# ColorMixingLamp.net
KiCad netlist of a schematic drawn in EAGLE
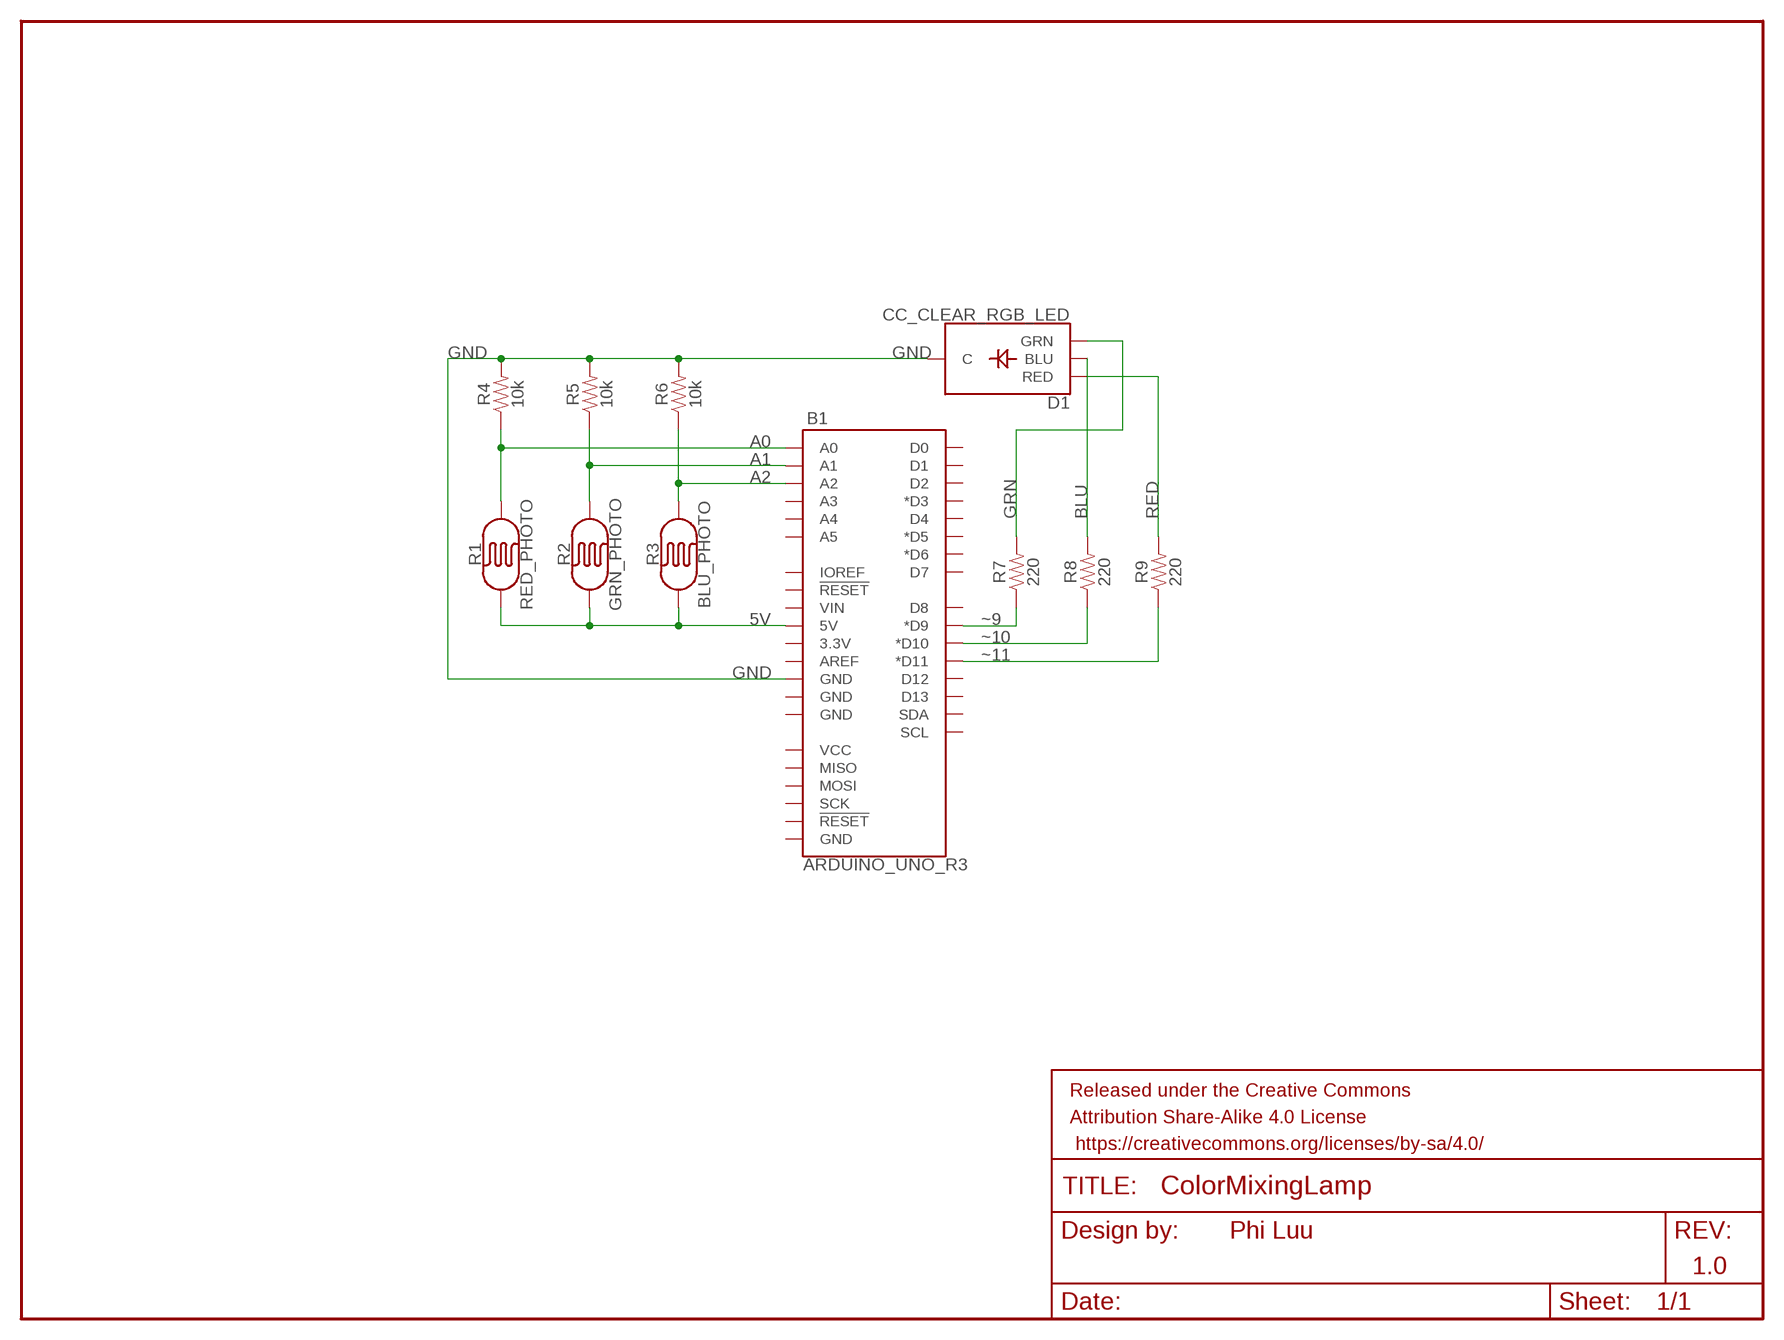
[diagram p0: schematic, sheet 1]

(export (version "E")
  (design (tool "Eeschema 10.0.6"))
  (components
    (comp (ref "B1")
      (value "ARDUINO_UNO_R3")
      (footprint "eagle-import:ARDUINO_R3")
      (libsource (lib "eagle-import") (part "ARDUINO_UNO_R3"))
    )
    (comp (ref "D1")
      (value "CC_CLEAR_RGB_LED")
      (footprint "eagle-import:LED-RGB-THRU")
      (libsource (lib "eagle-import") (part "LED-RGB-CCCLEAR"))
    )
    (comp (ref "FRAME1")
      (value "FRAME-LETTER")
      (footprint "eagle-import:CREATIVE_COMMONS")
      (libsource (lib "eagle-import") (part "FRAME-LETTER"))
    )
    (comp (ref "R1")
      (value "RED_PHOTO")
      (footprint "eagle-import:PHOTOCELL")
      (libsource (lib "eagle-import") (part "PHOTOCELLPTH"))
    )
    (comp (ref "R2")
      (value "GRN_PHOTO")
      (footprint "eagle-import:PHOTOCELL")
      (libsource (lib "eagle-import") (part "PHOTOCELLPTH"))
    )
    (comp (ref "R3")
      (value "BLU_PHOTO")
      (footprint "eagle-import:PHOTOCELL")
      (libsource (lib "eagle-import") (part "PHOTOCELLPTH"))
    )
    (comp (ref "R4")
      (value "10k")
      (footprint "eagle-import:AXIAL-0.3")
      (libsource (lib "eagle-import") (part "10KOHM-HORIZ-1/4W-5%"))
    )
    (comp (ref "R5")
      (value "10k")
      (footprint "eagle-import:AXIAL-0.3")
      (libsource (lib "eagle-import") (part "10KOHM-HORIZ-1/4W-5%"))
    )
    (comp (ref "R6")
      (value "10k")
      (footprint "eagle-import:AXIAL-0.3")
      (libsource (lib "eagle-import") (part "10KOHM-HORIZ-1/4W-5%"))
    )
    (comp (ref "R7")
      (value "220")
      (footprint "eagle-import:AXIAL-0.3")
      (libsource (lib "eagle-import") (part "1KOHM-HORIZ-1/4W-5%"))
    )
    (comp (ref "R8")
      (value "220")
      (footprint "eagle-import:AXIAL-0.3")
      (libsource (lib "eagle-import") (part "1KOHM-HORIZ-1/4W-5%"))
    )
    (comp (ref "R9")
      (value "220")
      (footprint "eagle-import:AXIAL-0.3")
      (libsource (lib "eagle-import") (part "1KOHM-HORIZ-1/4W-5%"))
    )
  )
  (nets
    (net (code "1") (name "/5V") (class "Default")
      (node (ref "B1") (pin "5V") (pinfunction "5V_5V") (pintype "bidirectional"))
      (node (ref "R1") (pin "1") (pinfunction "P$1_1") (pintype "bidirectional"))
      (node (ref "R2") (pin "1") (pinfunction "P$1_1") (pintype "bidirectional"))
      (node (ref "R3") (pin "1") (pinfunction "P$1_1") (pintype "bidirectional"))
    )
    (net (code "2") (name "/A0") (class "Default")
      (node (ref "B1") (pin "A0") (pinfunction "A0_A0") (pintype "bidirectional"))
      (node (ref "R1") (pin "2") (pinfunction "P$2_2") (pintype "bidirectional"))
      (node (ref "R4") (pin "P$1") (pinfunction "1_P$1") (pintype "passive"))
    )
    (net (code "3") (name "/A1") (class "Default")
      (node (ref "B1") (pin "A1") (pinfunction "A1_A1") (pintype "bidirectional"))
      (node (ref "R2") (pin "2") (pinfunction "P$2_2") (pintype "bidirectional"))
      (node (ref "R5") (pin "P$1") (pinfunction "1_P$1") (pintype "passive"))
    )
    (net (code "4") (name "/A2") (class "Default")
      (node (ref "B1") (pin "A2") (pinfunction "A2_A2") (pintype "bidirectional"))
      (node (ref "R3") (pin "2") (pinfunction "P$2_2") (pintype "bidirectional"))
      (node (ref "R6") (pin "P$1") (pinfunction "1_P$1") (pintype "passive"))
    )
    (net (code "5") (name "/BLU") (class "Default")
      (node (ref "D1") (pin "4") (pinfunction "BLU_4") (pintype "bidirectional"))
      (node (ref "R8") (pin "P$2") (pinfunction "2_P$2") (pintype "passive"))
    )
    (net (code "6") (name "/GND") (class "Default")
      (node (ref "B1") (pin "GND@4") (pinfunction "GND_GND@4") (pintype "bidirectional"))
      (node (ref "D1") (pin "2") (pinfunction "C_2") (pintype "bidirectional"))
      (node (ref "R4") (pin "P$2") (pinfunction "2_P$2") (pintype "passive"))
      (node (ref "R5") (pin "P$2") (pinfunction "2_P$2") (pintype "passive"))
      (node (ref "R6") (pin "P$2") (pinfunction "2_P$2") (pintype "passive"))
    )
    (net (code "7") (name "/GRN") (class "Default")
      (node (ref "D1") (pin "3") (pinfunction "GRN_3") (pintype "bidirectional"))
      (node (ref "R7") (pin "P$2") (pinfunction "2_P$2") (pintype "passive"))
    )
    (net (code "8") (name "/RED") (class "Default")
      (node (ref "D1") (pin "1") (pinfunction "RED_1") (pintype "bidirectional"))
      (node (ref "R9") (pin "P$2") (pinfunction "2_P$2") (pintype "passive"))
    )
    (net (code "9") (name "/~{9}") (class "Default")
      (node (ref "B1") (pin "D9") (pinfunction "*D9_D9") (pintype "bidirectional"))
      (node (ref "R7") (pin "P$1") (pinfunction "1_P$1") (pintype "passive"))
    )
    (net (code "10") (name "/~{10}") (class "Default")
      (node (ref "B1") (pin "D10") (pinfunction "*D10_D10") (pintype "bidirectional"))
      (node (ref "R8") (pin "P$1") (pinfunction "1_P$1") (pintype "passive"))
    )
    (net (code "11") (name "/~{11}") (class "Default")
      (node (ref "B1") (pin "D11") (pinfunction "*D11_D11") (pintype "bidirectional"))
      (node (ref "R9") (pin "P$1") (pinfunction "1_P$1") (pintype "passive"))
    )
    (net (code "12") (name "unconnected-(B1-*D3-PadD3)") (class "Default")
      (node (ref "B1") (pin "D3") (pinfunction "*D3_D3") (pintype "bidirectional"))
    )
    (net (code "13") (name "unconnected-(B1-*D5-PadD5)") (class "Default")
      (node (ref "B1") (pin "D5") (pinfunction "*D5_D5") (pintype "bidirectional"))
    )
    (net (code "14") (name "unconnected-(B1-*D6-PadD6)") (class "Default")
      (node (ref "B1") (pin "D6") (pinfunction "*D6_D6") (pintype "bidirectional"))
    )
    (net (code "15") (name "unconnected-(B1-GND-PadGND@1)") (class "Default")
      (node (ref "B1") (pin "GND@1") (pinfunction "GND_GND@1") (pintype "bidirectional"))
    )
    (net (code "16") (name "unconnected-(B1-GND-PadGND@2)") (class "Default")
      (node (ref "B1") (pin "GND@2") (pinfunction "GND_GND@2") (pintype "bidirectional"))
    )
    (net (code "17") (name "unconnected-(B1-GND-PadGND@3)") (class "Default")
      (node (ref "B1") (pin "GND@3") (pinfunction "GND_GND@3") (pintype "bidirectional"))
    )
    (net (code "18") (name "unconnected-(B1-Pad3.3V)") (class "Default")
      (node (ref "B1") (pin "3.3V") (pinfunction "3.3V_3.3V") (pintype "bidirectional"))
    )
    (net (code "19") (name "unconnected-(B1-PadA3)") (class "Default")
      (node (ref "B1") (pin "A3") (pinfunction "A3_A3") (pintype "bidirectional"))
    )
    (net (code "20") (name "unconnected-(B1-PadA4)") (class "Default")
      (node (ref "B1") (pin "A4") (pinfunction "A4_A4") (pintype "bidirectional"))
    )
    (net (code "21") (name "unconnected-(B1-PadA5)") (class "Default")
      (node (ref "B1") (pin "A5") (pinfunction "A5_A5") (pintype "bidirectional"))
    )
    (net (code "22") (name "unconnected-(B1-PadAREF)") (class "Default")
      (node (ref "B1") (pin "AREF") (pinfunction "AREF_AREF") (pintype "bidirectional"))
    )
    (net (code "23") (name "unconnected-(B1-PadD0)") (class "Default")
      (node (ref "B1") (pin "D0") (pinfunction "D0_D0") (pintype "bidirectional"))
    )
    (net (code "24") (name "unconnected-(B1-PadD1)") (class "Default")
      (node (ref "B1") (pin "D1") (pinfunction "D1_D1") (pintype "bidirectional"))
    )
    (net (code "25") (name "unconnected-(B1-PadD2)") (class "Default")
      (node (ref "B1") (pin "D2") (pinfunction "D2_D2") (pintype "bidirectional"))
    )
    (net (code "26") (name "unconnected-(B1-PadD4)") (class "Default")
      (node (ref "B1") (pin "D4") (pinfunction "D4_D4") (pintype "bidirectional"))
    )
    (net (code "27") (name "unconnected-(B1-PadD7)") (class "Default")
      (node (ref "B1") (pin "D7") (pinfunction "D7_D7") (pintype "bidirectional"))
    )
    (net (code "28") (name "unconnected-(B1-PadD8)") (class "Default")
      (node (ref "B1") (pin "D8") (pinfunction "D8_D8") (pintype "bidirectional"))
    )
    (net (code "29") (name "unconnected-(B1-PadD12)") (class "Default")
      (node (ref "B1") (pin "D12") (pinfunction "D12_D12") (pintype "bidirectional"))
    )
    (net (code "30") (name "unconnected-(B1-PadD13)") (class "Default")
      (node (ref "B1") (pin "D13") (pinfunction "D13_D13") (pintype "bidirectional"))
    )
    (net (code "31") (name "unconnected-(B1-PadIOREF)") (class "Default")
      (node (ref "B1") (pin "IOREF") (pinfunction "IOREF_IOREF") (pintype "bidirectional"))
    )
    (net (code "32") (name "unconnected-(B1-PadMISO)") (class "Default")
      (node (ref "B1") (pin "MISO") (pinfunction "MISO_MISO") (pintype "bidirectional"))
    )
    (net (code "33") (name "unconnected-(B1-PadMOSI)") (class "Default")
      (node (ref "B1") (pin "MOSI") (pinfunction "MOSI_MOSI") (pintype "bidirectional"))
    )
    (net (code "34") (name "unconnected-(B1-PadSCK)") (class "Default")
      (node (ref "B1") (pin "SCK") (pinfunction "SCK_SCK") (pintype "bidirectional"))
    )
    (net (code "35") (name "unconnected-(B1-PadSCL)") (class "Default")
      (node (ref "B1") (pin "SCL") (pinfunction "SCL_SCL") (pintype "bidirectional"))
    )
    (net (code "36") (name "unconnected-(B1-PadSDA)") (class "Default")
      (node (ref "B1") (pin "SDA") (pinfunction "SDA_SDA") (pintype "bidirectional"))
    )
    (net (code "37") (name "unconnected-(B1-PadVCC)") (class "Default")
      (node (ref "B1") (pin "VCC") (pinfunction "VCC_VCC") (pintype "bidirectional"))
    )
    (net (code "38") (name "unconnected-(B1-PadVIN)") (class "Default")
      (node (ref "B1") (pin "VIN") (pinfunction "VIN_VIN") (pintype "bidirectional"))
    )
    (net (code "39") (name "unconnected-(B1-~{RESET}-PadRESET@1)") (class "Default")
      (node (ref "B1") (pin "RESET@1") (pinfunction "~{RESET}_RESET@1") (pintype "bidirectional"))
    )
    (net (code "40") (name "unconnected-(B1-~{RESET}-PadRESET@2)") (class "Default")
      (node (ref "B1") (pin "RESET@2") (pinfunction "~{RESET}_RESET@2") (pintype "bidirectional"))
    )
  )
)
